# JAM.net
KiCad netlist of a schematic drawn in Altium Designer
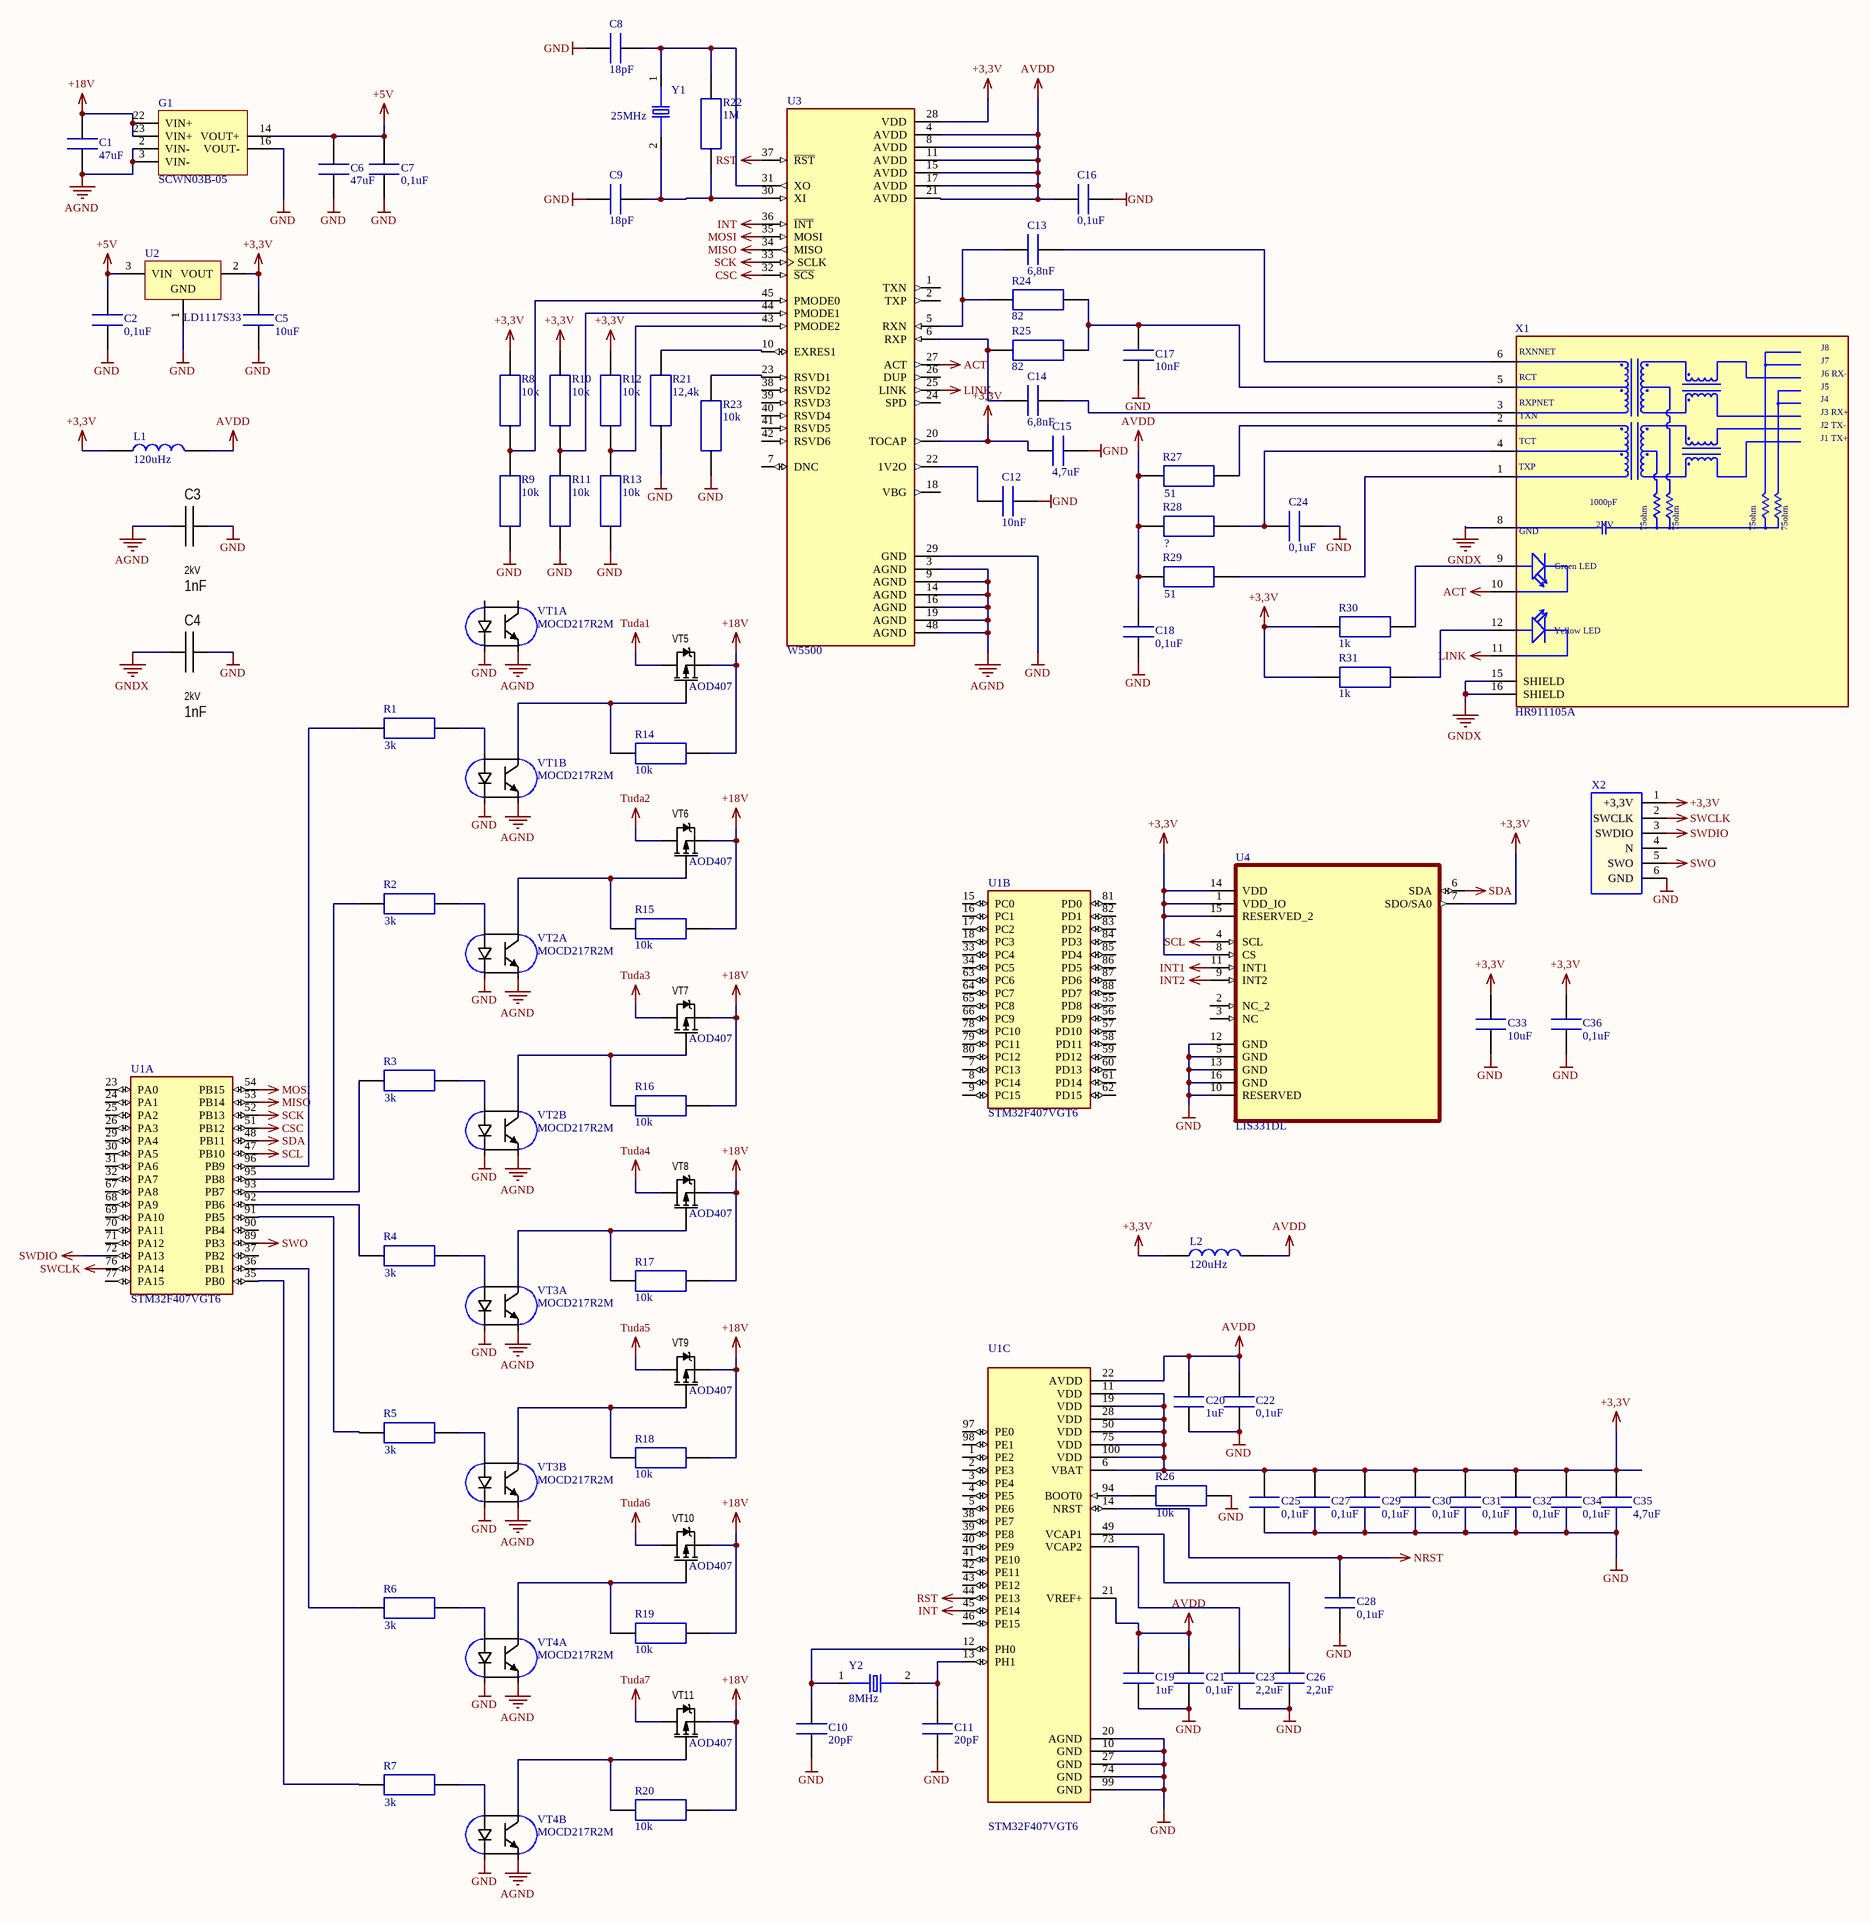
[diagram p0: JAM.SchDoc]

(export (version "E")
  (design (tool "Eeschema 10.0.6"))
  (components
    (comp (ref "C1") (value "47uF") (footprint "0603") (libsource (lib "Schlib1") (part "Cap")))
    (comp (ref "C2") (value "0,1uF") (footprint "0603") (libsource (lib "Schlib1") (part "Cap")))
    (comp (ref "C3")
      (value "1nF")
      (footprint "CAP: 1206")
      (fields
        (field (name "MANUFACTURER") "Yageo")
        (field (name "PARTNUMBER") "CC1206KRX7R9BB104")
        (field (name "VALUEMANUFACTURERPARTNUMBER") "Ceramic capacitor, 1nF, X7R, ±10%, 2kV, 1206, -55...+125°C")
        (field (name "VOLTAGE") "2kV")
      )
      (libsource (lib "capacitor") (part "Ceramic_1206"))
    )
    (comp (ref "C4")
      (value "1nF")
      (footprint "CAP: 1206")
      (fields
        (field (name "MANUFACTURER") "Yageo")
        (field (name "PARTNUMBER") "CC1206KRX7R9BB104")
        (field (name "VALUEMANUFACTURERPARTNUMBER") "Ceramic capacitor, 1nF, X7R, ±10%, 2kV, 1206, -55...+125°C")
        (field (name "VOLTAGE") "2kV")
      )
      (libsource (lib "capacitor") (part "Ceramic_1206"))
    )
    (comp (ref "C5") (value "10uF") (footprint "0603") (libsource (lib "Schlib1") (part "Cap")))
    (comp (ref "C6") (value "47uF") (footprint "0603") (libsource (lib "Schlib1") (part "Cap")))
    (comp (ref "C7") (value "0,1uF") (footprint "0603") (libsource (lib "Schlib1") (part "Cap")))
    (comp (ref "C8") (value "18pF") (footprint "0603") (libsource (lib "Schlib1") (part "Cap")))
    (comp (ref "C9") (value "18pF") (footprint "0603") (libsource (lib "Schlib1") (part "Cap")))
    (comp (ref "C10") (value "20pF") (footprint "0603") (libsource (lib "Schlib1") (part "Cap")))
    (comp (ref "C11") (value "20pF") (footprint "0603") (libsource (lib "Schlib1") (part "Cap")))
    (comp (ref "C12") (value "10nF") (footprint "0603") (libsource (lib "Schlib1") (part "Cap")))
    (comp (ref "C13") (value "6,8nF") (footprint "0603") (libsource (lib "Schlib1") (part "Cap")))
    (comp (ref "C14") (value "6,8nF") (footprint "0603") (libsource (lib "Schlib1") (part "Cap")))
    (comp (ref "C15") (value "4,7uF") (footprint "0603") (libsource (lib "Schlib1") (part "Cap")))
    (comp (ref "C16") (value "0,1uF") (footprint "0603") (libsource (lib "Schlib1") (part "Cap")))
    (comp (ref "C17") (value "10nF") (footprint "0603") (libsource (lib "Schlib1") (part "Cap")))
    (comp (ref "C18") (value "0,1uF") (footprint "0603") (libsource (lib "Schlib1") (part "Cap")))
    (comp (ref "C19") (value "1uF") (footprint "0603") (libsource (lib "Schlib1") (part "Cap")))
    (comp (ref "C20") (value "1uF") (footprint "0603") (libsource (lib "Schlib1") (part "Cap")))
    (comp (ref "C21") (value "0,1uF") (footprint "0603") (libsource (lib "Schlib1") (part "Cap")))
    (comp (ref "C22") (value "0,1uF") (footprint "0603") (libsource (lib "Schlib1") (part "Cap")))
    (comp (ref "C23") (value "2,2uF") (footprint "0603") (libsource (lib "Schlib1") (part "Cap")))
    (comp (ref "C24") (value "0,1uF") (footprint "0603") (libsource (lib "Schlib1") (part "Cap")))
    (comp (ref "C25") (value "0,1uF") (footprint "0603") (libsource (lib "Schlib1") (part "Cap")))
    (comp (ref "C26") (value "2,2uF") (footprint "0603") (libsource (lib "Schlib1") (part "Cap")))
    (comp (ref "C27") (value "0,1uF") (footprint "0603") (libsource (lib "Schlib1") (part "Cap")))
    (comp (ref "C28") (value "0,1uF") (footprint "0603") (libsource (lib "Schlib1") (part "Cap")))
    (comp (ref "C29") (value "0,1uF") (footprint "0603") (libsource (lib "Schlib1") (part "Cap")))
    (comp (ref "C30") (value "0,1uF") (footprint "0603") (libsource (lib "Schlib1") (part "Cap")))
    (comp (ref "C31") (value "0,1uF") (footprint "0603") (libsource (lib "Schlib1") (part "Cap")))
    (comp (ref "C32") (value "0,1uF") (footprint "0603") (libsource (lib "Schlib1") (part "Cap")))
    (comp (ref "C33") (value "10uF") (footprint "0603") (libsource (lib "Schlib1") (part "Cap")))
    (comp (ref "C34") (value "0,1uF") (footprint "0603") (libsource (lib "Schlib1") (part "Cap")))
    (comp (ref "C35") (value "4,7uF") (footprint "0603") (libsource (lib "Schlib1") (part "Cap")))
    (comp (ref "C36") (value "0,1uF") (footprint "0603") (libsource (lib "Schlib1") (part "Cap")))
    (comp (ref "G1")
      (value "SCWN03B-05")
      (footprint "DIP")
      (description "DC-DC Regulated Converter DIP")
      (libsource (lib "Schlib1") (part "SCWN03B-05"))
    )
    (comp (ref "L1") (value "120uHz") (footprint "0603") (libsource (lib "Schlib1") (part "Ind")))
    (comp (ref "L2") (value "120uHz") (footprint "0603") (libsource (lib "Schlib1") (part "Ind")))
    (comp (ref "R1") (value "3k") (footprint "0603") (libsource (lib "Schlib1") (part "Rez")))
    (comp (ref "R2") (value "3k") (footprint "0603") (libsource (lib "Schlib1") (part "Rez")))
    (comp (ref "R3") (value "3k") (footprint "0603") (libsource (lib "Schlib1") (part "Rez")))
    (comp (ref "R4") (value "3k") (footprint "0603") (libsource (lib "Schlib1") (part "Rez")))
    (comp (ref "R5") (value "3k") (footprint "0603") (libsource (lib "Schlib1") (part "Rez")))
    (comp (ref "R6") (value "3k") (footprint "0603") (libsource (lib "Schlib1") (part "Rez")))
    (comp (ref "R7") (value "3k") (footprint "0603") (libsource (lib "Schlib1") (part "Rez")))
    (comp (ref "R8") (value "10k") (footprint "0603") (libsource (lib "Schlib1") (part "Rez")))
    (comp (ref "R9") (value "10k") (footprint "0603") (libsource (lib "Schlib1") (part "Rez")))
    (comp (ref "R10") (value "10k") (footprint "0603") (libsource (lib "Schlib1") (part "Rez")))
    (comp (ref "R11") (value "10k") (footprint "0603") (libsource (lib "Schlib1") (part "Rez")))
    (comp (ref "R12") (value "10k") (footprint "0603") (libsource (lib "Schlib1") (part "Rez")))
    (comp (ref "R13") (value "10k") (footprint "0603") (libsource (lib "Schlib1") (part "Rez")))
    (comp (ref "R14") (value "10k") (footprint "0603") (libsource (lib "Schlib1") (part "Rez")))
    (comp (ref "R15") (value "10k") (footprint "0603") (libsource (lib "Schlib1") (part "Rez")))
    (comp (ref "R16") (value "10k") (footprint "0603") (libsource (lib "Schlib1") (part "Rez")))
    (comp (ref "R17") (value "10k") (footprint "0603") (libsource (lib "Schlib1") (part "Rez")))
    (comp (ref "R18") (value "10k") (footprint "0603") (libsource (lib "Schlib1") (part "Rez")))
    (comp (ref "R19") (value "10k") (footprint "0603") (libsource (lib "Schlib1") (part "Rez")))
    (comp (ref "R20") (value "10k") (footprint "0603") (libsource (lib "Schlib1") (part "Rez")))
    (comp (ref "R21") (value "12,4k") (footprint "0603") (libsource (lib "Schlib1") (part "Rez")))
    (comp (ref "R22") (value "1M") (footprint "0603") (libsource (lib "Schlib1") (part "Rez")))
    (comp (ref "R23") (value "10k") (footprint "0603") (libsource (lib "Schlib1") (part "Rez")))
    (comp (ref "R24") (value "82") (footprint "0603") (libsource (lib "Schlib1") (part "Rez")))
    (comp (ref "R25") (value "82") (footprint "0603") (libsource (lib "Schlib1") (part "Rez")))
    (comp (ref "R26") (value "10k") (footprint "0603") (libsource (lib "Schlib1") (part "Rez")))
    (comp (ref "R27") (value "51") (footprint "0603") (libsource (lib "Schlib1") (part "Rez")))
    (comp (ref "R28") (value "?") (footprint "0603") (libsource (lib "Schlib1") (part "Rez")))
    (comp (ref "R29") (value "51") (footprint "0603") (libsource (lib "Schlib1") (part "Rez")))
    (comp (ref "R30") (value "1k") (footprint "0603") (libsource (lib "Schlib1") (part "Rez")))
    (comp (ref "R31") (value "1k") (footprint "0603") (libsource (lib "Schlib1") (part "Rez")))
    (comp (ref "U1")
      (value "STM32F407VGT6")
      (footprint "QFP50P1600X1600X160-100N")
      (description "ARMÂ® CortexÂ®-M4 STM32F4 Microcontroller IC 32-Bit 168MHz 1MB _1M x 8_ FLASH 100-LQFP _14x14_")
      (fields (field (name "MF") "STMicroelectronics"))
      (libsource (lib "STM32F407VGT6") (part "STM32F407VGT6"))
    )
    (comp (ref "U2")
      (value "LD1117S33")
      (footprint "SOT-223L")
      (description "Adjustable and fixed low drop positive voltage regulator, SOT-223")
      (libsource (lib "Schlib1") (part "LD1117S33"))
    )
    (comp (ref "U3")
      (value "W5500")
      (footprint "QFP50P900X900X160-48N")
      (description "Socket Contact Silver 17-20 AWG Crimp Power")
      (fields (field (name "MF") "WIZnet"))
      (libsource (lib "W5500") (part "W5500"))
    )
    (comp (ref "U4")
      (value "LIS331DL")
      (footprint "LGA16R50P3X5_300X300X100")
      (description "ÐÐºÑÐµÐ»ÐµÑ€Ð¾Ð¼ÐµÑ‚Ñ€ Ð¿Ð¾ Ð¾ÑÑÐ¼ X, Y, Z Â± 2g, 4g, 8g 25 Ð“Ñ† ~ 500 Ð“Ñ† 16-LGA (3x3)")
      (fields (field (name "MF") "STMicroelectronics"))
      (libsource (lib "LIS331DL") (part "LIS331DL"))
    )
    (comp (ref "VT1") (value "MOCD217R2M") (footprint "SO-8") (libsource (lib "Schlib1") (part "Opto")))
    (comp (ref "VT2") (value "MOCD217R2M") (footprint "SO-8") (libsource (lib "Schlib1") (part "Opto")))
    (comp (ref "VT3") (value "MOCD217R2M") (footprint "SO-8") (libsource (lib "Schlib1") (part "Opto")))
    (comp (ref "VT4") (value "MOCD217R2M") (footprint "SO-8") (libsource (lib "Schlib1") (part "Opto")))
    (comp (ref "VT5")
      (value "AOD407")
      (footprint "SOT23")
      (fields
        (field (name "MANUFACTURER") "Infineon Technologies")
        (field (name "VALUEMANUFACTURERPARTNUMBER") "MOSFET P-channel transistor, 20V, 2.6A, 2.9nC, 2.5W, 135mOhm, 220pF, SOT-23, -55...+150°C")
        (field (name "PARTNUMBER") "IRLML2246TRPBF")
      )
      (libsource (lib "transistor") (part "MOSFET_P_123"))
    )
    (comp (ref "VT6")
      (value "AOD407")
      (footprint "SOT23")
      (fields
        (field (name "MANUFACTURER") "Infineon Technologies")
        (field (name "VALUEMANUFACTURERPARTNUMBER") "MOSFET P-channel transistor, 20V, 2.6A, 2.9nC, 2.5W, 135mOhm, 220pF, SOT-23, -55...+150°C")
        (field (name "PARTNUMBER") "IRLML2246TRPBF")
      )
      (libsource (lib "transistor") (part "MOSFET_P_123"))
    )
    (comp (ref "VT7")
      (value "AOD407")
      (footprint "SOT23")
      (fields
        (field (name "MANUFACTURER") "Infineon Technologies")
        (field (name "VALUEMANUFACTURERPARTNUMBER") "MOSFET P-channel transistor, 20V, 2.6A, 2.9nC, 2.5W, 135mOhm, 220pF, SOT-23, -55...+150°C")
        (field (name "PARTNUMBER") "IRLML2246TRPBF")
      )
      (libsource (lib "transistor") (part "MOSFET_P_123"))
    )
    (comp (ref "VT8")
      (value "AOD407")
      (footprint "SOT23")
      (fields
        (field (name "MANUFACTURER") "Infineon Technologies")
        (field (name "VALUEMANUFACTURERPARTNUMBER") "MOSFET P-channel transistor, 20V, 2.6A, 2.9nC, 2.5W, 135mOhm, 220pF, SOT-23, -55...+150°C")
        (field (name "PARTNUMBER") "IRLML2246TRPBF")
      )
      (libsource (lib "transistor") (part "MOSFET_P_123"))
    )
    (comp (ref "VT9")
      (value "AOD407")
      (footprint "SOT23")
      (fields
        (field (name "MANUFACTURER") "Infineon Technologies")
        (field (name "VALUEMANUFACTURERPARTNUMBER") "MOSFET P-channel transistor, 20V, 2.6A, 2.9nC, 2.5W, 135mOhm, 220pF, SOT-23, -55...+150°C")
        (field (name "PARTNUMBER") "IRLML2246TRPBF")
      )
      (libsource (lib "transistor") (part "MOSFET_P_123"))
    )
    (comp (ref "VT10")
      (value "AOD407")
      (footprint "SOT23")
      (fields
        (field (name "MANUFACTURER") "Infineon Technologies")
        (field (name "VALUEMANUFACTURERPARTNUMBER") "MOSFET P-channel transistor, 20V, 2.6A, 2.9nC, 2.5W, 135mOhm, 220pF, SOT-23, -55...+150°C")
        (field (name "PARTNUMBER") "IRLML2246TRPBF")
      )
      (libsource (lib "transistor") (part "MOSFET_P_123"))
    )
    (comp (ref "VT11")
      (value "AOD407")
      (footprint "SOT23")
      (fields
        (field (name "MANUFACTURER") "Infineon Technologies")
        (field (name "VALUEMANUFACTURERPARTNUMBER") "MOSFET P-channel transistor, 20V, 2.6A, 2.9nC, 2.5W, 135mOhm, 220pF, SOT-23, -55...+150°C")
        (field (name "PARTNUMBER") "IRLML2246TRPBF")
      )
      (libsource (lib "transistor") (part "MOSFET_P_123"))
    )
    (comp (ref "X1")
      (value "HR911105A")
      (footprint "HANRUN_HR911105A")
      (description "HR911105A Ethernet Interface Arduino Platform Evaluation Expansion Board")
      (fields (field (name "MF") "DFRobot"))
      (libsource (lib "HR911105A") (part "HR911105A"))
    )
    (comp (ref "X2") (value "PROG") (footprint "3x2x2,54") (libsource (lib "Schlib1") (part "PROG")))
    (comp (ref "Y1")
      (value "25MHz")
      (footprint "XTAL1170X500X450")
      (description "24.576MHz Â±30ppm Crystal 20pF 30 Ohms HC-49/US")
      (fields (field (name "MF") "Fox Electronics") (field (name "MP") "FOXSDLF/245F-20"))
      (libsource (lib "FOXSDLF_245F-20") (part "FOXSDLF/245F-20"))
    )
    (comp (ref "Y2")
      (value "8MHz")
      (footprint "XTAL1170X500X450")
      (description "24.576MHz Â±30ppm Crystal 20pF 30 Ohms HC-49/US")
      (fields (field (name "MF") "Fox Electronics") (field (name "MP") "FOXSDLF/245F-20"))
      (libsource (lib "FOXSDLF_245F-20") (part "FOXSDLF/245F-20"))
    )
  )
  (nets
    (net (code "1") (name "+3,3V") (class "Default")
      (node (ref "C15") (pin "2") (pinfunction "2_2") (pintype "passive"))
      (node (ref "C25") (pin "2") (pinfunction "2_2") (pintype "passive"))
      (node (ref "C27") (pin "2") (pinfunction "2_2") (pintype "passive"))
      (node (ref "C29") (pin "2") (pinfunction "2_2") (pintype "passive"))
      (node (ref "C30") (pin "2") (pinfunction "2_2") (pintype "passive"))
      (node (ref "C31") (pin "2") (pinfunction "2_2") (pintype "passive"))
      (node (ref "C32") (pin "2") (pinfunction "2_2") (pintype "passive"))
      (node (ref "C33") (pin "2") (pinfunction "2_2") (pintype "passive"))
      (node (ref "C34") (pin "2") (pinfunction "2_2") (pintype "passive"))
      (node (ref "C35") (pin "2") (pinfunction "2_2") (pintype "passive"))
      (node (ref "C36") (pin "2") (pinfunction "2_2") (pintype "passive"))
      (node (ref "C5") (pin "2") (pinfunction "2_2") (pintype "passive"))
      (node (ref "L1") (pin "1") (pinfunction "1_1") (pintype "passive"))
      (node (ref "L2") (pin "1") (pinfunction "1_1") (pintype "passive"))
      (node (ref "R10") (pin "2") (pinfunction "2_2") (pintype "passive"))
      (node (ref "R12") (pin "2") (pinfunction "2_2") (pintype "passive"))
      (node (ref "R30") (pin "1") (pinfunction "1_1") (pintype "passive"))
      (node (ref "R31") (pin "1") (pinfunction "1_1") (pintype "passive"))
      (node (ref "R8") (pin "2") (pinfunction "2_2") (pintype "passive"))
      (node (ref "U1") (pin "100") (pinfunction "VDD_100") (pintype "power_in"))
      (node (ref "U1") (pin "11") (pinfunction "VDD_11") (pintype "power_in"))
      (node (ref "U1") (pin "19") (pinfunction "VDD_19") (pintype "power_in"))
      (node (ref "U1") (pin "28") (pinfunction "VDD_28") (pintype "power_in"))
      (node (ref "U1") (pin "50") (pinfunction "VDD_50") (pintype "power_in"))
      (node (ref "U1") (pin "6") (pinfunction "VBAT_6") (pintype "power_in"))
      (node (ref "U1") (pin "75") (pinfunction "VDD_75") (pintype "power_in"))
      (node (ref "U2") (pin "2") (pinfunction "VOUT_2") (pintype "power_in"))
      (node (ref "U3") (pin "20") (pinfunction "TOCAP_20") (pintype "output"))
      (node (ref "U3") (pin "28") (pinfunction "VDD_28") (pintype "power_in"))
      (node (ref "U4") (pin "1") (pinfunction "VDD_IO_1") (pintype "power_in"))
      (node (ref "U4") (pin "14") (pinfunction "VDD_14") (pintype "power_in"))
      (node (ref "U4") (pin "15") (pinfunction "RESERVED_2_15") (pintype "power_in"))
      (node (ref "U4") (pin "7") (pinfunction "SDO/SA0_7") (pintype "output"))
      (node (ref "U4") (pin "8") (pinfunction "CS_8") (pintype "input"))
      (node (ref "X2") (pin "1") (pinfunction "+3,3V_1") (pintype "passive"))
    )
    (net (code "2") (name "+5V") (class "Default")
      (node (ref "C2") (pin "2") (pinfunction "2_2") (pintype "passive"))
      (node (ref "C6") (pin "2") (pinfunction "2_2") (pintype "passive"))
      (node (ref "C7") (pin "2") (pinfunction "2_2") (pintype "passive"))
      (node (ref "G1") (pin "14") (pinfunction "VOUT+_14") (pintype "power_in"))
      (node (ref "U2") (pin "3") (pinfunction "VIN_3") (pintype "power_in"))
    )
    (net (code "3") (name "+18V") (class "Default")
      (node (ref "C1") (pin "2") (pinfunction "2_2") (pintype "passive"))
      (node (ref "G1") (pin "22") (pinfunction "VIN+_22") (pintype "power_in"))
      (node (ref "G1") (pin "23") (pinfunction "VIN+_23") (pintype "power_in"))
      (node (ref "R14") (pin "2") (pinfunction "2_2") (pintype "passive"))
      (node (ref "R15") (pin "2") (pinfunction "2_2") (pintype "passive"))
      (node (ref "R16") (pin "2") (pinfunction "2_2") (pintype "passive"))
      (node (ref "R17") (pin "2") (pinfunction "2_2") (pintype "passive"))
      (node (ref "R18") (pin "2") (pinfunction "2_2") (pintype "passive"))
      (node (ref "R19") (pin "2") (pinfunction "2_2") (pintype "passive"))
      (node (ref "R20") (pin "2") (pinfunction "2_2") (pintype "passive"))
      (node (ref "VT10") (pin "3") (pinfunction "S_3") (pintype "passive"))
      (node (ref "VT11") (pin "3") (pinfunction "S_3") (pintype "passive"))
      (node (ref "VT5") (pin "3") (pinfunction "S_3") (pintype "passive"))
      (node (ref "VT6") (pin "3") (pinfunction "S_3") (pintype "passive"))
      (node (ref "VT7") (pin "3") (pinfunction "S_3") (pintype "passive"))
      (node (ref "VT8") (pin "3") (pinfunction "S_3") (pintype "passive"))
      (node (ref "VT9") (pin "3") (pinfunction "S_3") (pintype "passive"))
    )
    (net (code "4") (name "ACT") (class "Default")
      (node (ref "U3") (pin "27") (pinfunction "ACT_27") (pintype "output"))
      (node (ref "X1") (pin "10") (pinfunction "ACT_10") (pintype "passive"))
    )
    (net (code "5") (name "AGND") (class "Default")
      (node (ref "C1") (pin "1") (pinfunction "1_1") (pintype "passive"))
      (node (ref "C3") (pin "1") (pinfunction "1_1") (pintype "passive"))
      (node (ref "G1") (pin "2") (pinfunction "VIN-_2") (pintype "power_in"))
      (node (ref "G1") (pin "3") (pinfunction "VIN-_3") (pintype "power_in"))
      (node (ref "U3") (pin "14") (pinfunction "AGND_14") (pintype "power_in"))
      (node (ref "U3") (pin "16") (pinfunction "AGND_16") (pintype "power_in"))
      (node (ref "U3") (pin "19") (pinfunction "AGND_19") (pintype "power_in"))
      (node (ref "U3") (pin "3") (pinfunction "AGND_3") (pintype "power_in"))
      (node (ref "U3") (pin "48") (pinfunction "AGND_48") (pintype "power_in"))
      (node (ref "U3") (pin "9") (pinfunction "AGND_9") (pintype "power_in"))
      (node (ref "VT1") (pin "5") (pinfunction "E2_5") (pintype "passive"))
      (node (ref "VT1") (pin "7") (pinfunction "E1_7") (pintype "passive"))
      (node (ref "VT2") (pin "5") (pinfunction "E2_5") (pintype "passive"))
      (node (ref "VT2") (pin "7") (pinfunction "E1_7") (pintype "passive"))
      (node (ref "VT3") (pin "5") (pinfunction "E2_5") (pintype "passive"))
      (node (ref "VT3") (pin "7") (pinfunction "E1_7") (pintype "passive"))
      (node (ref "VT4") (pin "5") (pinfunction "E2_5") (pintype "passive"))
      (node (ref "VT4") (pin "7") (pinfunction "E1_7") (pintype "passive"))
    )
    (net (code "6") (name "AVDD") (class "Default")
      (node (ref "C16") (pin "2") (pinfunction "2_2") (pintype "passive"))
      (node (ref "C18") (pin "1") (pinfunction "1_1") (pintype "passive"))
      (node (ref "C19") (pin "2") (pinfunction "2_2") (pintype "passive"))
      (node (ref "C20") (pin "2") (pinfunction "2_2") (pintype "passive"))
      (node (ref "C21") (pin "2") (pinfunction "2_2") (pintype "passive"))
      (node (ref "C22") (pin "2") (pinfunction "2_2") (pintype "passive"))
      (node (ref "L1") (pin "2") (pinfunction "2_2") (pintype "passive"))
      (node (ref "L2") (pin "2") (pinfunction "2_2") (pintype "passive"))
      (node (ref "R27") (pin "1") (pinfunction "1_1") (pintype "passive"))
      (node (ref "R28") (pin "1") (pinfunction "1_1") (pintype "passive"))
      (node (ref "R29") (pin "1") (pinfunction "1_1") (pintype "passive"))
      (node (ref "U1") (pin "21") (pinfunction "VREF+_21") (pintype "power_in"))
      (node (ref "U1") (pin "22") (pinfunction "AVDD_22") (pintype "power_in"))
      (node (ref "U3") (pin "11") (pinfunction "AVDD_11") (pintype "power_in"))
      (node (ref "U3") (pin "15") (pinfunction "AVDD_15") (pintype "power_in"))
      (node (ref "U3") (pin "17") (pinfunction "AVDD_17") (pintype "power_in"))
      (node (ref "U3") (pin "21") (pinfunction "AVDD_21") (pintype "power_in"))
      (node (ref "U3") (pin "4") (pinfunction "AVDD_4") (pintype "power_in"))
      (node (ref "U3") (pin "8") (pinfunction "AVDD_8") (pintype "power_in"))
    )
    (net (code "7") (name "CSC") (class "Default")
      (node (ref "U1") (pin "51") (pinfunction "PB12_51") (pintype "bidirectional"))
      (node (ref "U3") (pin "32") (pinfunction "~{SCS}_32") (pintype "input"))
    )
    (net (code "8") (name "GND") (class "Default")
      (node (ref "C10") (pin "1") (pinfunction "1_1") (pintype "passive"))
      (node (ref "C11") (pin "1") (pinfunction "1_1") (pintype "passive"))
      (node (ref "C12") (pin "1") (pinfunction "1_1") (pintype "passive"))
      (node (ref "C15") (pin "1") (pinfunction "1_1") (pintype "passive"))
      (node (ref "C16") (pin "1") (pinfunction "1_1") (pintype "passive"))
      (node (ref "C17") (pin "2") (pinfunction "2_2") (pintype "passive"))
      (node (ref "C18") (pin "2") (pinfunction "2_2") (pintype "passive"))
      (node (ref "C19") (pin "1") (pinfunction "1_1") (pintype "passive"))
      (node (ref "C2") (pin "1") (pinfunction "1_1") (pintype "passive"))
      (node (ref "C20") (pin "1") (pinfunction "1_1") (pintype "passive"))
      (node (ref "C21") (pin "1") (pinfunction "1_1") (pintype "passive"))
      (node (ref "C22") (pin "1") (pinfunction "1_1") (pintype "passive"))
      (node (ref "C23") (pin "1") (pinfunction "1_1") (pintype "passive"))
      (node (ref "C24") (pin "2") (pinfunction "2_2") (pintype "passive"))
      (node (ref "C25") (pin "1") (pinfunction "1_1") (pintype "passive"))
      (node (ref "C26") (pin "1") (pinfunction "1_1") (pintype "passive"))
      (node (ref "C27") (pin "1") (pinfunction "1_1") (pintype "passive"))
      (node (ref "C28") (pin "1") (pinfunction "1_1") (pintype "passive"))
      (node (ref "C29") (pin "1") (pinfunction "1_1") (pintype "passive"))
      (node (ref "C3") (pin "2") (pinfunction "2_2") (pintype "passive"))
      (node (ref "C30") (pin "1") (pinfunction "1_1") (pintype "passive"))
      (node (ref "C31") (pin "1") (pinfunction "1_1") (pintype "passive"))
      (node (ref "C32") (pin "1") (pinfunction "1_1") (pintype "passive"))
      (node (ref "C33") (pin "1") (pinfunction "1_1") (pintype "passive"))
      (node (ref "C34") (pin "1") (pinfunction "1_1") (pintype "passive"))
      (node (ref "C35") (pin "1") (pinfunction "1_1") (pintype "passive"))
      (node (ref "C36") (pin "1") (pinfunction "1_1") (pintype "passive"))
      (node (ref "C4") (pin "2") (pinfunction "2_2") (pintype "passive"))
      (node (ref "C5") (pin "1") (pinfunction "1_1") (pintype "passive"))
      (node (ref "C6") (pin "1") (pinfunction "1_1") (pintype "passive"))
      (node (ref "C7") (pin "1") (pinfunction "1_1") (pintype "passive"))
      (node (ref "C8") (pin "1") (pinfunction "1_1") (pintype "passive"))
      (node (ref "C9") (pin "1") (pinfunction "1_1") (pintype "passive"))
      (node (ref "G1") (pin "16") (pinfunction "VOUT-_16") (pintype "passive"))
      (node (ref "R11") (pin "1") (pinfunction "1_1") (pintype "passive"))
      (node (ref "R13") (pin "1") (pinfunction "1_1") (pintype "passive"))
      (node (ref "R21") (pin "1") (pinfunction "1_1") (pintype "passive"))
      (node (ref "R23") (pin "1") (pinfunction "1_1") (pintype "passive"))
      (node (ref "R26") (pin "2") (pinfunction "2_2") (pintype "passive"))
      (node (ref "R9") (pin "1") (pinfunction "1_1") (pintype "passive"))
      (node (ref "U1") (pin "10") (pinfunction "GND_10") (pintype "power_in"))
      (node (ref "U1") (pin "20") (pinfunction "AGND_20") (pintype "power_in"))
      (node (ref "U1") (pin "27") (pinfunction "GND_27") (pintype "power_in"))
      (node (ref "U1") (pin "74") (pinfunction "GND_74") (pintype "power_in"))
      (node (ref "U1") (pin "99") (pinfunction "GND_99") (pintype "power_in"))
      (node (ref "U2") (pin "1") (pinfunction "GND_1") (pintype "power_in"))
      (node (ref "U3") (pin "29") (pinfunction "GND_29") (pintype "passive"))
      (node (ref "U4") (pin "10") (pinfunction "RESERVED_10") (pintype "passive"))
      (node (ref "U4") (pin "12") (pinfunction "GND_12") (pintype "passive"))
      (node (ref "U4") (pin "13") (pinfunction "GND_13") (pintype "passive"))
      (node (ref "U4") (pin "16") (pinfunction "GND_16") (pintype "passive"))
      (node (ref "U4") (pin "5") (pinfunction "GND_5") (pintype "passive"))
      (node (ref "VT1") (pin "2") (pinfunction "Ca1_2") (pintype "passive"))
      (node (ref "VT1") (pin "4") (pinfunction "Ca2_4") (pintype "passive"))
      (node (ref "VT2") (pin "2") (pinfunction "Ca1_2") (pintype "passive"))
      (node (ref "VT2") (pin "4") (pinfunction "Ca2_4") (pintype "passive"))
      (node (ref "VT3") (pin "2") (pinfunction "Ca1_2") (pintype "passive"))
      (node (ref "VT3") (pin "4") (pinfunction "Ca2_4") (pintype "passive"))
      (node (ref "VT4") (pin "2") (pinfunction "Ca1_2") (pintype "passive"))
      (node (ref "VT4") (pin "4") (pinfunction "Ca2_4") (pintype "passive"))
      (node (ref "X2") (pin "6") (pinfunction "GND_6") (pintype "passive"))
    )
    (net (code "9") (name "GNDX") (class "Default")
      (node (ref "C4") (pin "1") (pinfunction "1_1") (pintype "passive"))
      (node (ref "X1") (pin "15") (pinfunction "SHIELD_15") (pintype "passive"))
      (node (ref "X1") (pin "16") (pinfunction "SHIELD_16") (pintype "passive"))
      (node (ref "X1") (pin "8") (pinfunction "GND_8") (pintype "power_in"))
    )
    (net (code "10") (name "INT") (class "Default")
      (node (ref "U1") (pin "45") (pinfunction "PE14_45") (pintype "bidirectional"))
      (node (ref "U3") (pin "36") (pinfunction "~{INT}_36") (pintype "input"))
    )
    (net (code "11") (name "INT1") (class "Default")
      (node (ref "U4") (pin "11") (pinfunction "INT1_11") (pintype "input"))
    )
    (net (code "12") (name "INT2") (class "Default")
      (node (ref "U4") (pin "9") (pinfunction "INT2_9") (pintype "input"))
    )
    (net (code "13") (name "LINK") (class "Default")
      (node (ref "U3") (pin "25") (pinfunction "LINK_25") (pintype "output"))
      (node (ref "X1") (pin "11") (pinfunction "LINK_11") (pintype "passive"))
    )
    (net (code "14") (name "MISO") (class "Default")
      (node (ref "U1") (pin "53") (pinfunction "PB14_53") (pintype "bidirectional"))
      (node (ref "U3") (pin "34") (pinfunction "MISO_34") (pintype "output"))
    )
    (net (code "15") (name "MOSI") (class "Default")
      (node (ref "U1") (pin "54") (pinfunction "PB15_54") (pintype "bidirectional"))
      (node (ref "U3") (pin "35") (pinfunction "MOSI_35") (pintype "input"))
    )
    (net (code "16") (name "NRST") (class "Default")
      (node (ref "C28") (pin "2") (pinfunction "2_2") (pintype "passive"))
      (node (ref "U1") (pin "14") (pinfunction "NRST_14") (pintype "bidirectional"))
    )
    (net (code "17") (name "Net-(U1A-PB0)") (class "Default")
      (node (ref "R7") (pin "1") (pinfunction "1_1") (pintype "passive"))
      (node (ref "U1") (pin "35") (pinfunction "PB0_35") (pintype "bidirectional"))
    )
    (net (code "18") (name "Net-(U1A-PB1)") (class "Default")
      (node (ref "R6") (pin "1") (pinfunction "1_1") (pintype "passive"))
      (node (ref "U1") (pin "36") (pinfunction "PB1_36") (pintype "bidirectional"))
    )
    (net (code "19") (name "Net-(U1A-PB5)") (class "Default")
      (node (ref "R5") (pin "1") (pinfunction "1_1") (pintype "passive"))
      (node (ref "U1") (pin "91") (pinfunction "PB5_91") (pintype "bidirectional"))
    )
    (net (code "20") (name "Net-(U1A-PB6)") (class "Default")
      (node (ref "R4") (pin "1") (pinfunction "1_1") (pintype "passive"))
      (node (ref "U1") (pin "92") (pinfunction "PB6_92") (pintype "bidirectional"))
    )
    (net (code "21") (name "Net-(U1A-PB7)") (class "Default")
      (node (ref "R3") (pin "1") (pinfunction "1_1") (pintype "passive"))
      (node (ref "U1") (pin "93") (pinfunction "PB7_93") (pintype "bidirectional"))
    )
    (net (code "22") (name "Net-(U1A-PB8)") (class "Default")
      (node (ref "R2") (pin "1") (pinfunction "1_1") (pintype "passive"))
      (node (ref "U1") (pin "95") (pinfunction "PB8_95") (pintype "bidirectional"))
    )
    (net (code "23") (name "Net-(U1A-PB9)") (class "Default")
      (node (ref "R1") (pin "1") (pinfunction "1_1") (pintype "passive"))
      (node (ref "U1") (pin "96") (pinfunction "PB9_96") (pintype "bidirectional"))
    )
    (net (code "24") (name "Net-(U1C-BOOT0)") (class "Default")
      (node (ref "R26") (pin "1") (pinfunction "1_1") (pintype "passive"))
      (node (ref "U1") (pin "94") (pinfunction "BOOT0_94") (pintype "input"))
    )
    (net (code "25") (name "Net-(U1C-PH0)") (class "Default")
      (node (ref "C10") (pin "2") (pinfunction "2_2") (pintype "passive"))
      (node (ref "U1") (pin "12") (pinfunction "PH0_12") (pintype "bidirectional"))
      (node (ref "Y2") (pin "1") (pintype "passive"))
    )
    (net (code "26") (name "Net-(U1C-PH1)") (class "Default")
      (node (ref "C11") (pin "2") (pinfunction "2_2") (pintype "passive"))
      (node (ref "U1") (pin "13") (pinfunction "PH1_13") (pintype "bidirectional"))
      (node (ref "Y2") (pin "2") (pintype "passive"))
    )
    (net (code "27") (name "Net-(U1C-VCAP1)") (class "Default")
      (node (ref "C26") (pin "2") (pinfunction "2_2") (pintype "passive"))
      (node (ref "U1") (pin "49") (pinfunction "VCAP1_49") (pintype "passive"))
    )
    (net (code "28") (name "Net-(U1C-VCAP2)") (class "Default")
      (node (ref "C23") (pin "2") (pinfunction "2_2") (pintype "passive"))
      (node (ref "U1") (pin "73") (pinfunction "VCAP2_73") (pintype "passive"))
    )
    (net (code "29") (name "Net-(U3-1V2O)") (class "Default")
      (node (ref "C12") (pin "2") (pinfunction "2_2") (pintype "passive"))
      (node (ref "U3") (pin "22") (pinfunction "1V2O_22") (pintype "output"))
    )
    (net (code "30") (name "Net-(U3-EXRES1)") (class "Default")
      (node (ref "R21") (pin "2") (pinfunction "2_2") (pintype "passive"))
      (node (ref "U3") (pin "10") (pinfunction "EXRES1_10") (pintype "bidirectional"))
    )
    (net (code "31") (name "Net-(U3-PMODE0)") (class "Default")
      (node (ref "R8") (pin "1") (pinfunction "1_1") (pintype "passive"))
      (node (ref "R9") (pin "2") (pinfunction "2_2") (pintype "passive"))
      (node (ref "U3") (pin "45") (pinfunction "PMODE0_45") (pintype "input"))
    )
    (net (code "32") (name "Net-(U3-PMODE1)") (class "Default")
      (node (ref "R10") (pin "1") (pinfunction "1_1") (pintype "passive"))
      (node (ref "R11") (pin "2") (pinfunction "2_2") (pintype "passive"))
      (node (ref "U3") (pin "44") (pinfunction "PMODE1_44") (pintype "input"))
    )
    (net (code "33") (name "Net-(U3-PMODE2)") (class "Default")
      (node (ref "R12") (pin "1") (pinfunction "1_1") (pintype "passive"))
      (node (ref "R13") (pin "2") (pinfunction "2_2") (pintype "passive"))
      (node (ref "U3") (pin "43") (pinfunction "PMODE2_43") (pintype "input"))
    )
    (net (code "34") (name "Net-(U3-RSVD1)") (class "Default")
      (node (ref "R23") (pin "2") (pinfunction "2_2") (pintype "passive"))
      (node (ref "U3") (pin "23") (pinfunction "RSVD1_23") (pintype "input"))
    )
    (net (code "35") (name "Net-(U3-RXN)") (class "Default")
      (node (ref "C13") (pin "2") (pinfunction "2_2") (pintype "passive"))
      (node (ref "R24") (pin "1") (pinfunction "1_1") (pintype "passive"))
      (node (ref "U3") (pin "5") (pinfunction "RXN_5") (pintype "input"))
    )
    (net (code "36") (name "Net-(U3-RXP)") (class "Default")
      (node (ref "C14") (pin "2") (pinfunction "2_2") (pintype "passive"))
      (node (ref "R25") (pin "1") (pinfunction "1_1") (pintype "passive"))
      (node (ref "U3") (pin "6") (pinfunction "RXP_6") (pintype "input"))
    )
    (net (code "37") (name "Net-(U3-XI)") (class "Default")
      (node (ref "C9") (pin "2") (pinfunction "2_2") (pintype "passive"))
      (node (ref "R22") (pin "2") (pinfunction "2_2") (pintype "passive"))
      (node (ref "U3") (pin "30") (pinfunction "XI_30") (pintype "input"))
      (node (ref "Y1") (pin "2") (pintype "passive"))
    )
    (net (code "38") (name "Net-(U3-XO)") (class "Default")
      (node (ref "C8") (pin "2") (pinfunction "2_2") (pintype "passive"))
      (node (ref "R22") (pin "1") (pinfunction "1_1") (pintype "passive"))
      (node (ref "U3") (pin "31") (pinfunction "XO_31") (pintype "output"))
      (node (ref "Y1") (pin "1") (pintype "passive"))
    )
    (net (code "39") (name "Net-(VT1B-A2)") (class "Default")
      (node (ref "R1") (pin "2") (pinfunction "2_2") (pintype "passive"))
      (node (ref "VT1") (pin "3") (pinfunction "A2_3") (pintype "passive"))
    )
    (net (code "40") (name "Net-(VT1B-C2)") (class "Default")
      (node (ref "R14") (pin "1") (pinfunction "1_1") (pintype "passive"))
      (node (ref "VT1") (pin "6") (pinfunction "C2_6") (pintype "passive"))
      (node (ref "VT5") (pin "1") (pinfunction "G_1") (pintype "passive"))
    )
    (net (code "41") (name "Net-(VT2A-A1)") (class "Default")
      (node (ref "R2") (pin "2") (pinfunction "2_2") (pintype "passive"))
      (node (ref "VT2") (pin "1") (pinfunction "A1_1") (pintype "passive"))
    )
    (net (code "42") (name "Net-(VT2A-C1)") (class "Default")
      (node (ref "R15") (pin "1") (pinfunction "1_1") (pintype "passive"))
      (node (ref "VT2") (pin "8") (pinfunction "C1_8") (pintype "passive"))
      (node (ref "VT6") (pin "1") (pinfunction "G_1") (pintype "passive"))
    )
    (net (code "43") (name "Net-(VT2B-A2)") (class "Default")
      (node (ref "R3") (pin "2") (pinfunction "2_2") (pintype "passive"))
      (node (ref "VT2") (pin "3") (pinfunction "A2_3") (pintype "passive"))
    )
    (net (code "44") (name "Net-(VT2B-C2)") (class "Default")
      (node (ref "R16") (pin "1") (pinfunction "1_1") (pintype "passive"))
      (node (ref "VT2") (pin "6") (pinfunction "C2_6") (pintype "passive"))
      (node (ref "VT7") (pin "1") (pinfunction "G_1") (pintype "passive"))
    )
    (net (code "45") (name "Net-(VT3A-A1)") (class "Default")
      (node (ref "R4") (pin "2") (pinfunction "2_2") (pintype "passive"))
      (node (ref "VT3") (pin "1") (pinfunction "A1_1") (pintype "passive"))
    )
    (net (code "46") (name "Net-(VT3A-C1)") (class "Default")
      (node (ref "R17") (pin "1") (pinfunction "1_1") (pintype "passive"))
      (node (ref "VT3") (pin "8") (pinfunction "C1_8") (pintype "passive"))
      (node (ref "VT8") (pin "1") (pinfunction "G_1") (pintype "passive"))
    )
    (net (code "47") (name "Net-(VT3B-A2)") (class "Default")
      (node (ref "R5") (pin "2") (pinfunction "2_2") (pintype "passive"))
      (node (ref "VT3") (pin "3") (pinfunction "A2_3") (pintype "passive"))
    )
    (net (code "48") (name "Net-(VT3B-C2)") (class "Default")
      (node (ref "R18") (pin "1") (pinfunction "1_1") (pintype "passive"))
      (node (ref "VT3") (pin "6") (pinfunction "C2_6") (pintype "passive"))
      (node (ref "VT9") (pin "1") (pinfunction "G_1") (pintype "passive"))
    )
    (net (code "49") (name "Net-(VT4A-A1)") (class "Default")
      (node (ref "R6") (pin "2") (pinfunction "2_2") (pintype "passive"))
      (node (ref "VT4") (pin "1") (pinfunction "A1_1") (pintype "passive"))
    )
    (net (code "50") (name "Net-(VT4B-A2)") (class "Default")
      (node (ref "R7") (pin "2") (pinfunction "2_2") (pintype "passive"))
      (node (ref "VT4") (pin "3") (pinfunction "A2_3") (pintype "passive"))
    )
    (net (code "51") (name "Net-(VT10-G)") (class "Default")
      (node (ref "R19") (pin "1") (pinfunction "1_1") (pintype "passive"))
      (node (ref "VT10") (pin "1") (pinfunction "G_1") (pintype "passive"))
      (node (ref "VT4") (pin "8") (pinfunction "C1_8") (pintype "passive"))
    )
    (net (code "52") (name "Net-(VT11-G)") (class "Default")
      (node (ref "R20") (pin "1") (pinfunction "1_1") (pintype "passive"))
      (node (ref "VT11") (pin "1") (pinfunction "G_1") (pintype "passive"))
      (node (ref "VT4") (pin "6") (pinfunction "C2_6") (pintype "passive"))
    )
    (net (code "53") (name "Net-(X1-GA)") (class "Default")
      (node (ref "R30") (pin "2") (pinfunction "2_2") (pintype "passive"))
      (node (ref "X1") (pin "9") (pinfunction "GA_9") (pintype "passive"))
    )
    (net (code "54") (name "Net-(X1-RCT)") (class "Default")
      (node (ref "C17") (pin "1") (pinfunction "1_1") (pintype "passive"))
      (node (ref "R24") (pin "2") (pinfunction "2_2") (pintype "passive"))
      (node (ref "R25") (pin "2") (pinfunction "2_2") (pintype "passive"))
      (node (ref "X1") (pin "5") (pinfunction "RCT_5") (pintype "passive"))
    )
    (net (code "55") (name "Net-(X1-RXNNET)") (class "Default")
      (node (ref "C13") (pin "1") (pinfunction "1_1") (pintype "passive"))
      (node (ref "X1") (pin "6") (pinfunction "RXNNET_6") (pintype "passive"))
    )
    (net (code "56") (name "Net-(X1-RXPNET)") (class "Default")
      (node (ref "C14") (pin "1") (pinfunction "1_1") (pintype "passive"))
      (node (ref "X1") (pin "3") (pinfunction "RXPNET_3") (pintype "passive"))
    )
    (net (code "57") (name "Net-(X1-TCT)") (class "Default")
      (node (ref "C24") (pin "1") (pinfunction "1_1") (pintype "passive"))
      (node (ref "R28") (pin "2") (pinfunction "2_2") (pintype "passive"))
      (node (ref "X1") (pin "4") (pinfunction "TCT_4") (pintype "passive"))
    )
    (net (code "58") (name "Net-(X1-TXN)") (class "Default")
      (node (ref "R27") (pin "2") (pinfunction "2_2") (pintype "passive"))
      (node (ref "X1") (pin "2") (pinfunction "TXN_2") (pintype "passive"))
    )
    (net (code "59") (name "Net-(X1-TXP)") (class "Default")
      (node (ref "R29") (pin "2") (pinfunction "2_2") (pintype "passive"))
      (node (ref "X1") (pin "1") (pinfunction "TXP_1") (pintype "passive"))
    )
    (net (code "60") (name "Net-(X1-YA)") (class "Default")
      (node (ref "R31") (pin "2") (pinfunction "2_2") (pintype "passive"))
      (node (ref "X1") (pin "12") (pinfunction "YA_12") (pintype "passive"))
    )
    (net (code "61") (name "RST") (class "Default")
      (node (ref "U1") (pin "44") (pinfunction "PE13_44") (pintype "bidirectional"))
      (node (ref "U3") (pin "37") (pinfunction "~{RST}_37") (pintype "input"))
    )
    (net (code "62") (name "SCK") (class "Default")
      (node (ref "U1") (pin "52") (pinfunction "PB13_52") (pintype "bidirectional"))
      (node (ref "U3") (pin "33") (pinfunction "SCLK_33") (pintype "input"))
    )
    (net (code "63") (name "SCL") (class "Default")
      (node (ref "U1") (pin "47") (pinfunction "PB10_47") (pintype "bidirectional"))
      (node (ref "U4") (pin "4") (pinfunction "SCL_4") (pintype "input"))
    )
    (net (code "64") (name "SDA") (class "Default")
      (node (ref "U1") (pin "48") (pinfunction "PB11_48") (pintype "bidirectional"))
      (node (ref "U4") (pin "6") (pinfunction "SDA_6") (pintype "bidirectional"))
    )
    (net (code "65") (name "SWCLK") (class "Default")
      (node (ref "U1") (pin "76") (pinfunction "PA14_76") (pintype "bidirectional"))
      (node (ref "X2") (pin "2") (pinfunction "SWCLK_2") (pintype "passive"))
    )
    (net (code "66") (name "SWDIO") (class "Default")
      (node (ref "U1") (pin "72") (pinfunction "PA13_72") (pintype "bidirectional"))
      (node (ref "X2") (pin "3") (pinfunction "SWDIO_3") (pintype "passive"))
    )
    (net (code "67") (name "SWO") (class "Default")
      (node (ref "U1") (pin "89") (pinfunction "PB3_89") (pintype "bidirectional"))
      (node (ref "X2") (pin "5") (pinfunction "SWO_5") (pintype "passive"))
    )
    (net (code "68") (name "Tuda1") (class "Default")
      (node (ref "VT5") (pin "2") (pinfunction "D_2") (pintype "passive"))
    )
    (net (code "69") (name "Tuda2") (class "Default")
      (node (ref "VT6") (pin "2") (pinfunction "D_2") (pintype "passive"))
    )
    (net (code "70") (name "Tuda3") (class "Default")
      (node (ref "VT7") (pin "2") (pinfunction "D_2") (pintype "passive"))
    )
    (net (code "71") (name "Tuda4") (class "Default")
      (node (ref "VT8") (pin "2") (pinfunction "D_2") (pintype "passive"))
    )
    (net (code "72") (name "Tuda5") (class "Default")
      (node (ref "VT9") (pin "2") (pinfunction "D_2") (pintype "passive"))
    )
    (net (code "73") (name "Tuda6") (class "Default")
      (node (ref "VT10") (pin "2") (pinfunction "D_2") (pintype "passive"))
    )
    (net (code "74") (name "Tuda7") (class "Default")
      (node (ref "VT11") (pin "2") (pinfunction "D_2") (pintype "passive"))
    )
    (net (code "75") (name "unconnected-(U1A-PA0-Pad23)") (class "Default")
      (node (ref "U1") (pin "23") (pinfunction "PA0_23") (pintype "bidirectional"))
    )
    (net (code "76") (name "unconnected-(U1A-PA1-Pad24)") (class "Default")
      (node (ref "U1") (pin "24") (pinfunction "PA1_24") (pintype "bidirectional"))
    )
    (net (code "77") (name "unconnected-(U1A-PA2-Pad25)") (class "Default")
      (node (ref "U1") (pin "25") (pinfunction "PA2_25") (pintype "bidirectional"))
    )
    (net (code "78") (name "unconnected-(U1A-PA3-Pad26)") (class "Default")
      (node (ref "U1") (pin "26") (pinfunction "PA3_26") (pintype "bidirectional"))
    )
    (net (code "79") (name "unconnected-(U1A-PA4-Pad29)") (class "Default")
      (node (ref "U1") (pin "29") (pinfunction "PA4_29") (pintype "bidirectional"))
    )
    (net (code "80") (name "unconnected-(U1A-PA5-Pad30)") (class "Default")
      (node (ref "U1") (pin "30") (pinfunction "PA5_30") (pintype "bidirectional"))
    )
    (net (code "81") (name "unconnected-(U1A-PA6-Pad31)") (class "Default")
      (node (ref "U1") (pin "31") (pinfunction "PA6_31") (pintype "bidirectional"))
    )
    (net (code "82") (name "unconnected-(U1A-PA7-Pad32)") (class "Default")
      (node (ref "U1") (pin "32") (pinfunction "PA7_32") (pintype "bidirectional"))
    )
    (net (code "83") (name "unconnected-(U1A-PA8-Pad67)") (class "Default")
      (node (ref "U1") (pin "67") (pinfunction "PA8_67") (pintype "bidirectional"))
    )
    (net (code "84") (name "unconnected-(U1A-PA9-Pad68)") (class "Default")
      (node (ref "U1") (pin "68") (pinfunction "PA9_68") (pintype "bidirectional"))
    )
    (net (code "85") (name "unconnected-(U1A-PA10-Pad69)") (class "Default")
      (node (ref "U1") (pin "69") (pinfunction "PA10_69") (pintype "bidirectional"))
    )
    (net (code "86") (name "unconnected-(U1A-PA11-Pad70)") (class "Default")
      (node (ref "U1") (pin "70") (pinfunction "PA11_70") (pintype "bidirectional"))
    )
    (net (code "87") (name "unconnected-(U1A-PA12-Pad71)") (class "Default")
      (node (ref "U1") (pin "71") (pinfunction "PA12_71") (pintype "bidirectional"))
    )
    (net (code "88") (name "unconnected-(U1A-PA15-Pad77)") (class "Default")
      (node (ref "U1") (pin "77") (pinfunction "PA15_77") (pintype "bidirectional"))
    )
    (net (code "89") (name "unconnected-(U1A-PB2-Pad37)") (class "Default")
      (node (ref "U1") (pin "37") (pinfunction "PB2_37") (pintype "bidirectional"))
    )
    (net (code "90") (name "unconnected-(U1A-PB4-Pad90)") (class "Default")
      (node (ref "U1") (pin "90") (pinfunction "PB4_90") (pintype "bidirectional"))
    )
    (net (code "91") (name "unconnected-(U1B-PC0-Pad15)") (class "Default")
      (node (ref "U1") (pin "15") (pinfunction "PC0_15") (pintype "bidirectional"))
    )
    (net (code "92") (name "unconnected-(U1B-PC1-Pad16)") (class "Default")
      (node (ref "U1") (pin "16") (pinfunction "PC1_16") (pintype "bidirectional"))
    )
    (net (code "93") (name "unconnected-(U1B-PC2-Pad17)") (class "Default")
      (node (ref "U1") (pin "17") (pinfunction "PC2_17") (pintype "bidirectional"))
    )
    (net (code "94") (name "unconnected-(U1B-PC3-Pad18)") (class "Default")
      (node (ref "U1") (pin "18") (pinfunction "PC3_18") (pintype "bidirectional"))
    )
    (net (code "95") (name "unconnected-(U1B-PC4-Pad33)") (class "Default")
      (node (ref "U1") (pin "33") (pinfunction "PC4_33") (pintype "bidirectional"))
    )
    (net (code "96") (name "unconnected-(U1B-PC5-Pad34)") (class "Default")
      (node (ref "U1") (pin "34") (pinfunction "PC5_34") (pintype "bidirectional"))
    )
    (net (code "97") (name "unconnected-(U1B-PC6-Pad63)") (class "Default")
      (node (ref "U1") (pin "63") (pinfunction "PC6_63") (pintype "bidirectional"))
    )
    (net (code "98") (name "unconnected-(U1B-PC7-Pad64)") (class "Default")
      (node (ref "U1") (pin "64") (pinfunction "PC7_64") (pintype "bidirectional"))
    )
    (net (code "99") (name "unconnected-(U1B-PC8-Pad65)") (class "Default")
      (node (ref "U1") (pin "65") (pinfunction "PC8_65") (pintype "bidirectional"))
    )
    (net (code "100") (name "unconnected-(U1B-PC9-Pad66)") (class "Default")
      (node (ref "U1") (pin "66") (pinfunction "PC9_66") (pintype "bidirectional"))
    )
    (net (code "101") (name "unconnected-(U1B-PC10-Pad78)") (class "Default")
      (node (ref "U1") (pin "78") (pinfunction "PC10_78") (pintype "bidirectional"))
    )
    (net (code "102") (name "unconnected-(U1B-PC11-Pad79)") (class "Default")
      (node (ref "U1") (pin "79") (pinfunction "PC11_79") (pintype "bidirectional"))
    )
    (net (code "103") (name "unconnected-(U1B-PC12-Pad80)") (class "Default")
      (node (ref "U1") (pin "80") (pinfunction "PC12_80") (pintype "bidirectional"))
    )
    (net (code "104") (name "unconnected-(U1B-PC13-Pad7)") (class "Default")
      (node (ref "U1") (pin "7") (pinfunction "PC13_7") (pintype "bidirectional"))
    )
    (net (code "105") (name "unconnected-(U1B-PC14-Pad8)") (class "Default")
      (node (ref "U1") (pin "8") (pinfunction "PC14_8") (pintype "bidirectional"))
    )
    (net (code "106") (name "unconnected-(U1B-PC15-Pad9)") (class "Default")
      (node (ref "U1") (pin "9") (pinfunction "PC15_9") (pintype "bidirectional"))
    )
    (net (code "107") (name "unconnected-(U1B-PD0-Pad81)") (class "Default")
      (node (ref "U1") (pin "81") (pinfunction "PD0_81") (pintype "bidirectional"))
    )
    (net (code "108") (name "unconnected-(U1B-PD1-Pad82)") (class "Default")
      (node (ref "U1") (pin "82") (pinfunction "PD1_82") (pintype "bidirectional"))
    )
    (net (code "109") (name "unconnected-(U1B-PD2-Pad83)") (class "Default")
      (node (ref "U1") (pin "83") (pinfunction "PD2_83") (pintype "bidirectional"))
    )
    (net (code "110") (name "unconnected-(U1B-PD3-Pad84)") (class "Default")
      (node (ref "U1") (pin "84") (pinfunction "PD3_84") (pintype "bidirectional"))
    )
    (net (code "111") (name "unconnected-(U1B-PD4-Pad85)") (class "Default")
      (node (ref "U1") (pin "85") (pinfunction "PD4_85") (pintype "bidirectional"))
    )
    (net (code "112") (name "unconnected-(U1B-PD5-Pad86)") (class "Default")
      (node (ref "U1") (pin "86") (pinfunction "PD5_86") (pintype "bidirectional"))
    )
    (net (code "113") (name "unconnected-(U1B-PD6-Pad87)") (class "Default")
      (node (ref "U1") (pin "87") (pinfunction "PD6_87") (pintype "bidirectional"))
    )
    (net (code "114") (name "unconnected-(U1B-PD7-Pad88)") (class "Default")
      (node (ref "U1") (pin "88") (pinfunction "PD7_88") (pintype "bidirectional"))
    )
    (net (code "115") (name "unconnected-(U1B-PD8-Pad55)") (class "Default")
      (node (ref "U1") (pin "55") (pinfunction "PD8_55") (pintype "bidirectional"))
    )
    (net (code "116") (name "unconnected-(U1B-PD9-Pad56)") (class "Default")
      (node (ref "U1") (pin "56") (pinfunction "PD9_56") (pintype "bidirectional"))
    )
    (net (code "117") (name "unconnected-(U1B-PD10-Pad57)") (class "Default")
      (node (ref "U1") (pin "57") (pinfunction "PD10_57") (pintype "bidirectional"))
    )
    (net (code "118") (name "unconnected-(U1B-PD11-Pad58)") (class "Default")
      (node (ref "U1") (pin "58") (pinfunction "PD11_58") (pintype "bidirectional"))
    )
    (net (code "119") (name "unconnected-(U1B-PD12-Pad59)") (class "Default")
      (node (ref "U1") (pin "59") (pinfunction "PD12_59") (pintype "bidirectional"))
    )
    (net (code "120") (name "unconnected-(U1B-PD13-Pad60)") (class "Default")
      (node (ref "U1") (pin "60") (pinfunction "PD13_60") (pintype "bidirectional"))
    )
    (net (code "121") (name "unconnected-(U1B-PD14-Pad61)") (class "Default")
      (node (ref "U1") (pin "61") (pinfunction "PD14_61") (pintype "bidirectional"))
    )
    (net (code "122") (name "unconnected-(U1B-PD15-Pad62)") (class "Default")
      (node (ref "U1") (pin "62") (pinfunction "PD15_62") (pintype "bidirectional"))
    )
    (net (code "123") (name "unconnected-(U1C-PE0-Pad97)") (class "Default")
      (node (ref "U1") (pin "97") (pinfunction "PE0_97") (pintype "bidirectional"))
    )
    (net (code "124") (name "unconnected-(U1C-PE1-Pad98)") (class "Default")
      (node (ref "U1") (pin "98") (pinfunction "PE1_98") (pintype "bidirectional"))
    )
    (net (code "125") (name "unconnected-(U1C-PE2-Pad1)") (class "Default")
      (node (ref "U1") (pin "1") (pinfunction "PE2_1") (pintype "bidirectional"))
    )
    (net (code "126") (name "unconnected-(U1C-PE3-Pad2)") (class "Default")
      (node (ref "U1") (pin "2") (pinfunction "PE3_2") (pintype "bidirectional"))
    )
    (net (code "127") (name "unconnected-(U1C-PE4-Pad3)") (class "Default")
      (node (ref "U1") (pin "3") (pinfunction "PE4_3") (pintype "bidirectional"))
    )
    (net (code "128") (name "unconnected-(U1C-PE5-Pad4)") (class "Default")
      (node (ref "U1") (pin "4") (pinfunction "PE5_4") (pintype "bidirectional"))
    )
    (net (code "129") (name "unconnected-(U1C-PE6-Pad5)") (class "Default")
      (node (ref "U1") (pin "5") (pinfunction "PE6_5") (pintype "bidirectional"))
    )
    (net (code "130") (name "unconnected-(U1C-PE7-Pad38)") (class "Default")
      (node (ref "U1") (pin "38") (pinfunction "PE7_38") (pintype "bidirectional"))
    )
    (net (code "131") (name "unconnected-(U1C-PE8-Pad39)") (class "Default")
      (node (ref "U1") (pin "39") (pinfunction "PE8_39") (pintype "bidirectional"))
    )
    (net (code "132") (name "unconnected-(U1C-PE9-Pad40)") (class "Default")
      (node (ref "U1") (pin "40") (pinfunction "PE9_40") (pintype "bidirectional"))
    )
    (net (code "133") (name "unconnected-(U1C-PE10-Pad41)") (class "Default")
      (node (ref "U1") (pin "41") (pinfunction "PE10_41") (pintype "bidirectional"))
    )
    (net (code "134") (name "unconnected-(U1C-PE11-Pad42)") (class "Default")
      (node (ref "U1") (pin "42") (pinfunction "PE11_42") (pintype "bidirectional"))
    )
    (net (code "135") (name "unconnected-(U1C-PE12-Pad43)") (class "Default")
      (node (ref "U1") (pin "43") (pinfunction "PE12_43") (pintype "bidirectional"))
    )
    (net (code "136") (name "unconnected-(U1C-PE15-Pad46)") (class "Default")
      (node (ref "U1") (pin "46") (pinfunction "PE15_46") (pintype "bidirectional"))
    )
    (net (code "137") (name "unconnected-(U3-DNC-Pad7)") (class "Default")
      (node (ref "U3") (pin "7") (pinfunction "DNC_7") (pintype "bidirectional"))
    )
    (net (code "138") (name "unconnected-(U3-DUP-Pad26)") (class "Default")
      (node (ref "U3") (pin "26") (pinfunction "DUP_26") (pintype "output"))
    )
    (net (code "139") (name "unconnected-(U3-RSVD2-Pad38)") (class "Default")
      (node (ref "U3") (pin "38") (pinfunction "RSVD2_38") (pintype "input"))
    )
    (net (code "140") (name "unconnected-(U3-RSVD3-Pad39)") (class "Default")
      (node (ref "U3") (pin "39") (pinfunction "RSVD3_39") (pintype "input"))
    )
    (net (code "141") (name "unconnected-(U3-RSVD4-Pad40)") (class "Default")
      (node (ref "U3") (pin "40") (pinfunction "RSVD4_40") (pintype "input"))
    )
    (net (code "142") (name "unconnected-(U3-RSVD5-Pad41)") (class "Default")
      (node (ref "U3") (pin "41") (pinfunction "RSVD5_41") (pintype "input"))
    )
    (net (code "143") (name "unconnected-(U3-RSVD6-Pad42)") (class "Default")
      (node (ref "U3") (pin "42") (pinfunction "RSVD6_42") (pintype "input"))
    )
    (net (code "144") (name "unconnected-(U3-SPD-Pad24)") (class "Default")
      (node (ref "U3") (pin "24") (pinfunction "SPD_24") (pintype "output"))
    )
    (net (code "145") (name "unconnected-(U3-TXN-Pad1)") (class "Default")
      (node (ref "U3") (pin "1") (pinfunction "TXN_1") (pintype "output"))
    )
    (net (code "146") (name "unconnected-(U3-TXP-Pad2)") (class "Default")
      (node (ref "U3") (pin "2") (pinfunction "TXP_2") (pintype "output"))
    )
    (net (code "147") (name "unconnected-(U3-VBG-Pad18)") (class "Default")
      (node (ref "U3") (pin "18") (pinfunction "VBG_18") (pintype "output"))
    )
    (net (code "148") (name "unconnected-(U4-NC-Pad3)") (class "Default")
      (node (ref "U4") (pin "3") (pinfunction "NC_3") (pintype "input"))
    )
    (net (code "149") (name "unconnected-(U4-NC_2-Pad2)") (class "Default")
      (node (ref "U4") (pin "2") (pinfunction "NC_2_2") (pintype "input"))
    )
    (net (code "150") (name "unconnected-(VT1A-A1-Pad1)") (class "Default")
      (node (ref "VT1") (pin "1") (pinfunction "A1_1") (pintype "passive"))
    )
    (net (code "151") (name "unconnected-(VT1A-C1-Pad8)") (class "Default")
      (node (ref "VT1") (pin "8") (pinfunction "C1_8") (pintype "passive"))
    )
    (net (code "152") (name "unconnected-(X2-N-Pad4)") (class "Default")
      (node (ref "X2") (pin "4") (pinfunction "N_4") (pintype "passive"))
    )
  )
)
